# pinghengche.net
KiCad netlist of a schematic drawn in Altium Designer
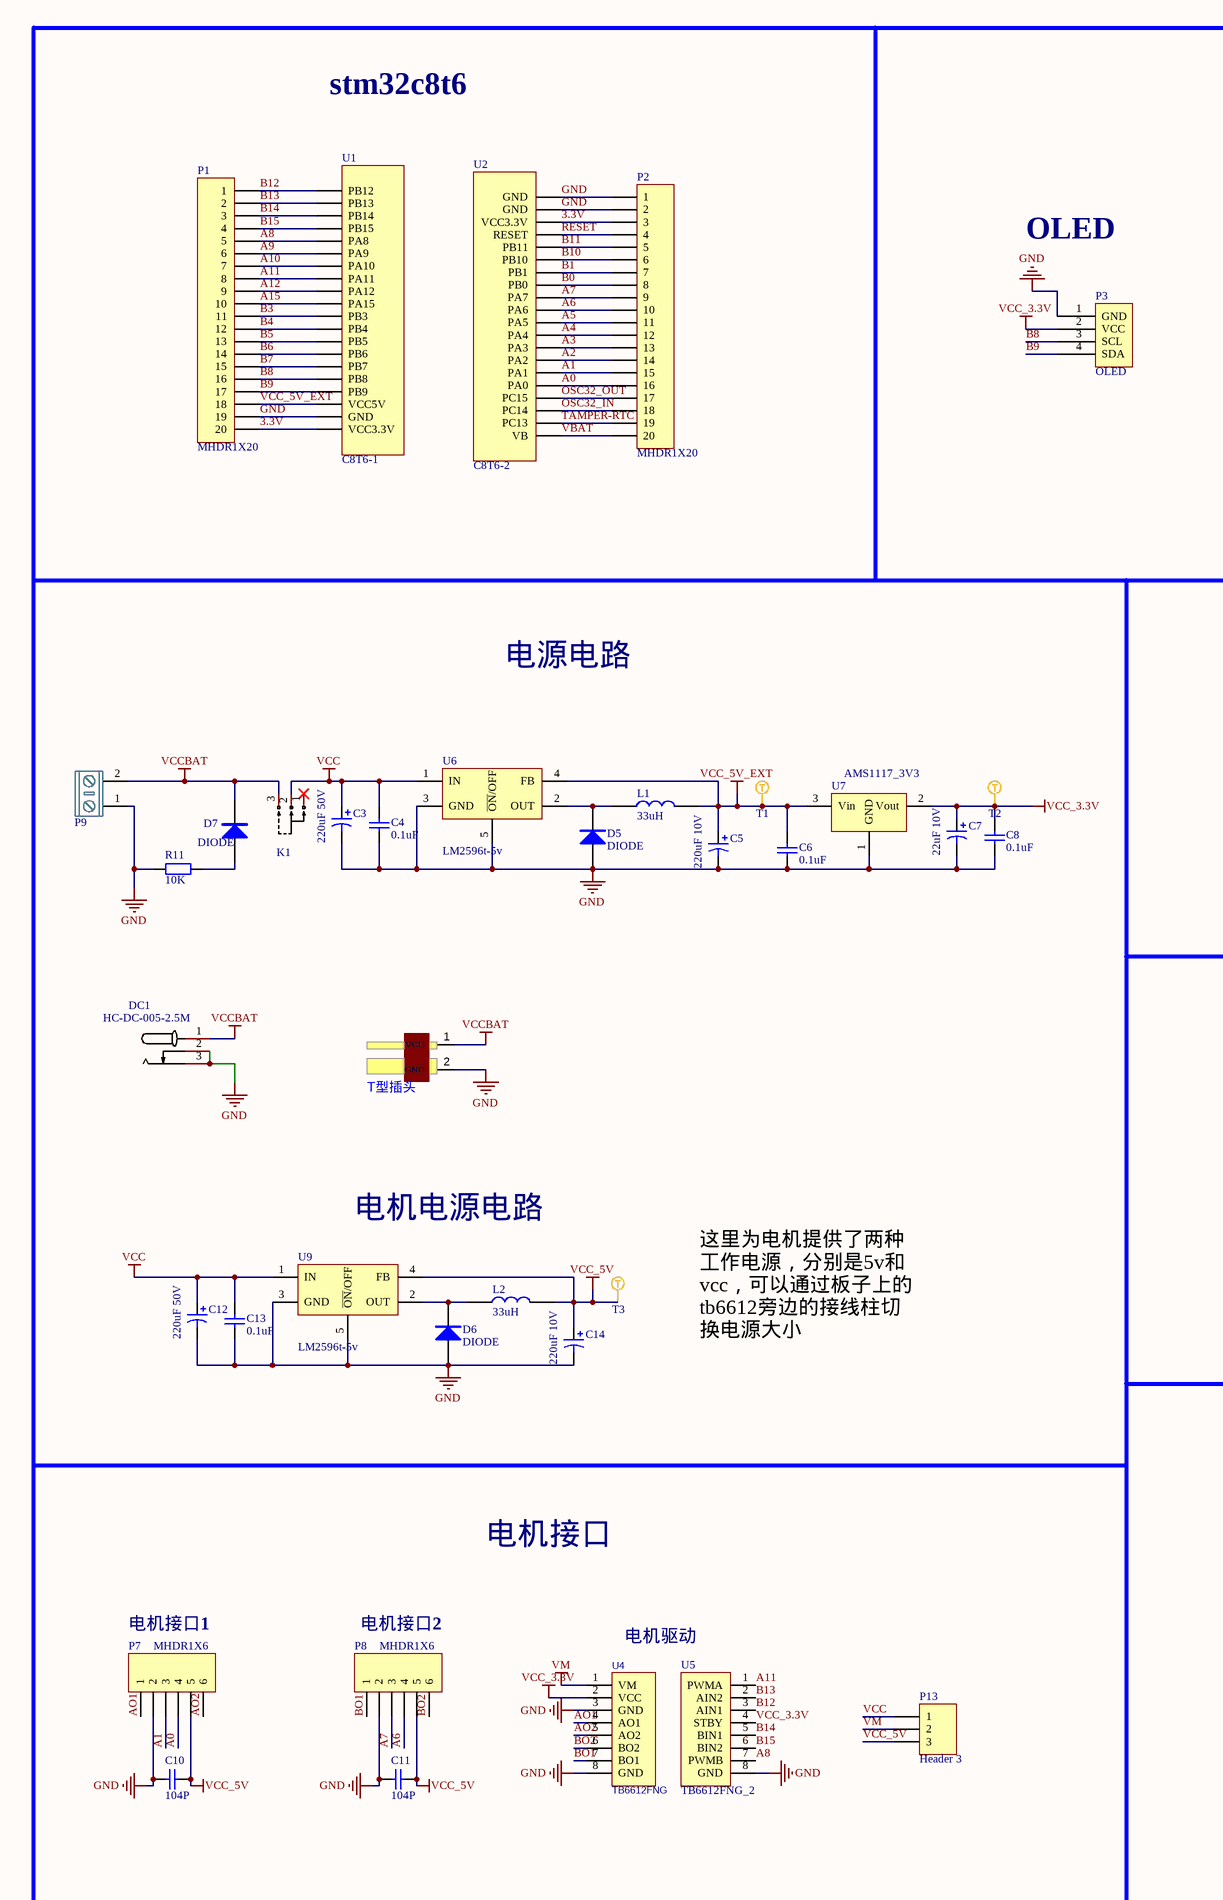
[diagram p0: pinghengche.SchDoc, left]
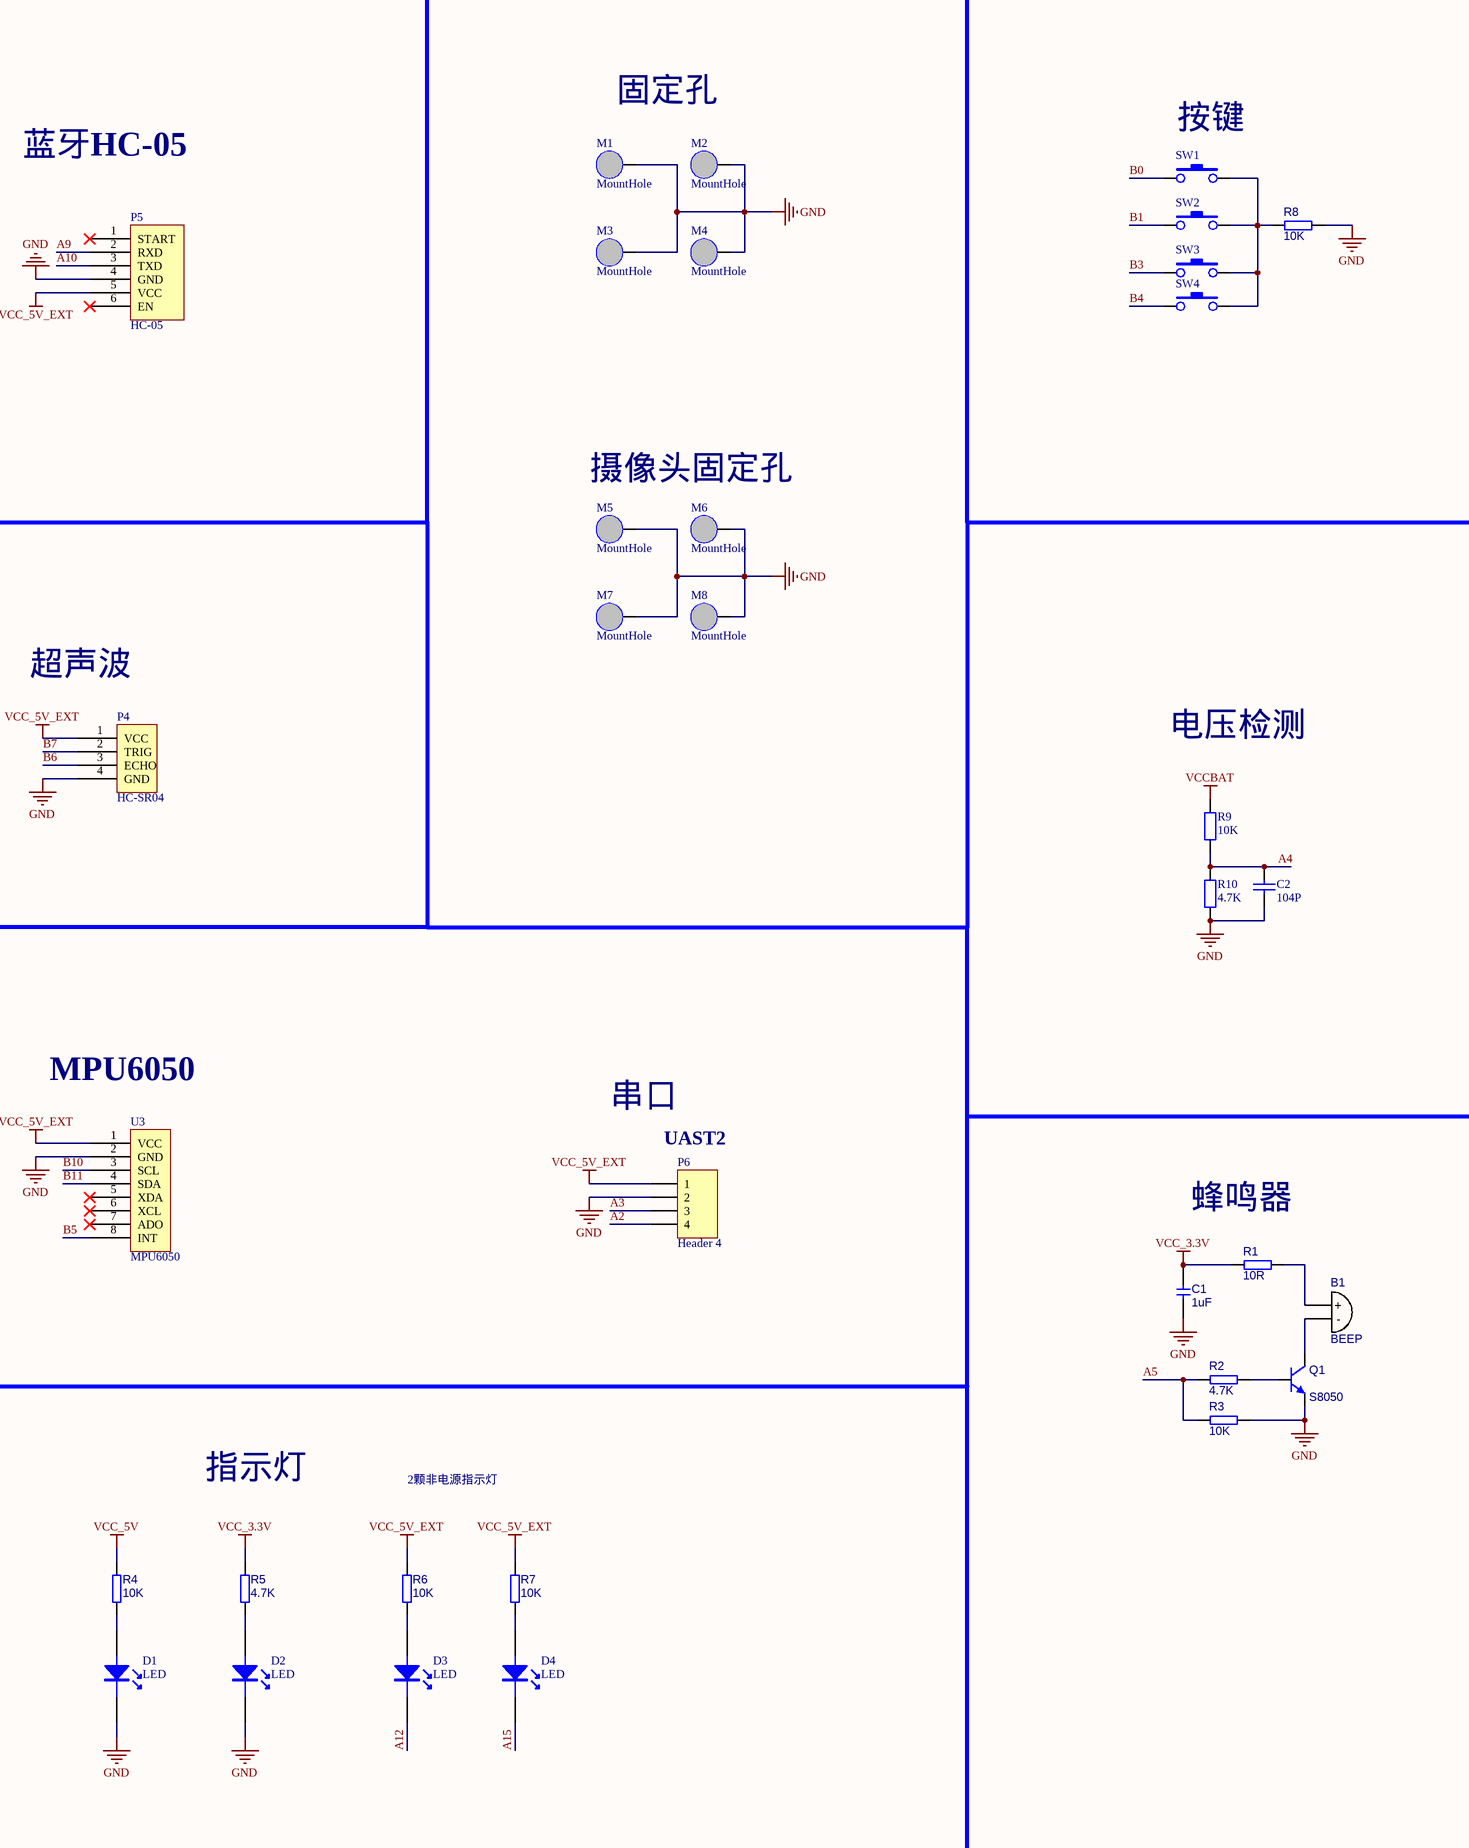
[diagram p1: pinghengche.SchDoc, right]

(export (version "E")
  (design (tool "Eeschema 10.0.6"))
  (components
    (comp (ref "B1")
      (value "BEEP")
      (footprint "BEEP 9x5.5mm")
      (description "蜂鸣器")
      (libsource (lib "pinghengchezihua") (part "BEEP"))
    )
    (comp (ref "C1")
      (value "1uF")
      (footprint "C0805")
      (description "贴片电容0805")
      (fields (field (name "Comment") "1uF  "))
      (libsource (lib "pinghengchezihua") (part "1uF 080516V X7R"))
    )
    (comp (ref "C2")
      (value "104P")
      (footprint "CAPC1608[0603]S-L")
      (description "0.1uf 贴片电容/MLCC电容")
      (libsource (lib "平衡小车") (part "C"))
    )
    (comp (ref "C3")
      (value "220uF 50V")
      (footprint "CAP-SMD_BD10.0-L10.3-W10.3-LS11.3-FD")
      (description "Polarized Capacitor (Radial)")
      (fields (field (name "Comment") "Cap Pol1") (field (name "PUBLISHER") "Altium Limited"))
      (libsource (lib "Miscellaneous Devices") (part "Cap Pol1"))
    )
    (comp (ref "C4")
      (value "0.1uF")
      (footprint "CAPC1608[0603]S-L")
      (description "Capacitor")
      (fields (field (name "Comment") "Cap") (field (name "PUBLISHER") "Altium Limited"))
      (libsource (lib "Miscellaneous Devices") (part "Cap"))
    )
    (comp (ref "C5")
      (value "220uF 10V")
      (footprint "7343")
      (description "Polarized Capacitor (Radial)")
      (fields (field (name "Comment") "Cap Pol1") (field (name "PUBLISHER") "Altium Limited"))
      (libsource (lib "Miscellaneous Devices") (part "Cap Pol1"))
    )
    (comp (ref "C6")
      (value "0.1uF")
      (footprint "CAPC1608[0603]S-L")
      (description "Capacitor")
      (fields (field (name "Comment") "Cap") (field (name "PUBLISHER") "Altium Limited"))
      (libsource (lib "Miscellaneous Devices") (part "Cap"))
    )
    (comp (ref "C7")
      (value "22uF 10V")
      (footprint "C3528")
      (description "Polarized Capacitor (Radial)")
      (fields (field (name "Comment") "Cap Pol1") (field (name "PUBLISHER") "Altium Limited"))
      (libsource (lib "Miscellaneous Devices") (part "Cap Pol1"))
    )
    (comp (ref "C8")
      (value "0.1uF")
      (footprint "CAPC1608[0603]S-L")
      (description "Capacitor")
      (fields (field (name "Comment") "Cap") (field (name "PUBLISHER") "Altium Limited"))
      (libsource (lib "Miscellaneous Devices") (part "Cap"))
    )
    (comp (ref "C10")
      (value "104P")
      (footprint "CAPC1608[0603]S-L")
      (description "0.1uf 贴片电容/MLCC电容")
      (libsource (lib "平衡小车") (part "C"))
    )
    (comp (ref "C11")
      (value "104P")
      (footprint "CAPC1608[0603]S-L")
      (description "0.1uf 贴片电容/MLCC电容")
      (libsource (lib "平衡小车") (part "C"))
    )
    (comp (ref "C12")
      (value "220uF 50V")
      (footprint "CAP-SMD_BD10.0-L10.3-W10.3-LS11.3-FD")
      (description "Polarized Capacitor (Radial)")
      (fields (field (name "Comment") "Cap Pol1") (field (name "PUBLISHER") "Altium Limited"))
      (libsource (lib "Miscellaneous Devices") (part "Cap Pol1"))
    )
    (comp (ref "C13")
      (value "0.1uF")
      (footprint "CAPC1608[0603]S-L")
      (description "Capacitor")
      (fields (field (name "Comment") "Cap") (field (name "PUBLISHER") "Altium Limited"))
      (libsource (lib "Miscellaneous Devices") (part "Cap"))
    )
    (comp (ref "C14")
      (value "220uF 10V")
      (footprint "7343")
      (description "Polarized Capacitor (Radial)")
      (fields (field (name "Comment") "Cap Pol1") (field (name "PUBLISHER") "Altium Limited"))
      (libsource (lib "Miscellaneous Devices") (part "Cap Pol1"))
    )
    (comp (ref "D1")
      (value "LED")
      (footprint "LED 0805G")
      (description "0805")
      (libsource (lib "pinghengchezihua") (part "LED"))
    )
    (comp (ref "D2")
      (value "LED")
      (footprint "LED 0805G")
      (description "0805")
      (libsource (lib "pinghengchezihua") (part "LED"))
    )
    (comp (ref "D3")
      (value "LED")
      (footprint "LED 0805G")
      (description "0805")
      (libsource (lib "pinghengchezihua") (part "LED"))
    )
    (comp (ref "D4")
      (value "LED")
      (footprint "LED 0805G")
      (description "0805")
      (libsource (lib "pinghengchezihua") (part "LED"))
    )
    (comp (ref "D5") (value "DIODE") (footprint "SS34") (libsource (lib "平衡小车") (part "DIODE")))
    (comp (ref "D6") (value "DIODE") (footprint "SS34") (libsource (lib "平衡小车") (part "DIODE")))
    (comp (ref "D7") (value "DIODE") (footprint "SS34") (libsource (lib "平衡小车") (part "DIODE")))
    (comp (ref "DC1")
      (value "HC-DC-005-2.5M")
      (footprint "DC-005")
      (fields (field (name "NAME") "HC-DC-005-2.5M") (field (name "MANUFACTURER") "HCTL(华灿天禄)"))
      (libsource (lib "altium-import") (part "root_0_HC-DC-005-2.5M_"))
    )
    (comp (ref "DCIN1")
      (value "T型插头")
      (footprint "Wired T-Header ThroughHole")
      (libsource (lib "pinghengchezihua") (part "T_Header"))
    )
    (comp (ref "K1")
      (value "HX SS12D10G4")
      (footprint "SS12D10")
      (description "单刀三档开关")
      (fields (field (name "MANUFACTURER") "hanxia(韩下)"))
      (libsource (lib "changyongwenyadianyuanmokuaixiugai") (part "HX SS12D10G4"))
    )
    (comp (ref "L1") (value "33uH") (footprint "0630 TPC 7*7*3") (libsource (lib "平衡小车") (part "Inductor")))
    (comp (ref "L2") (value "33uH") (footprint "0630 TPC 7*7*3") (libsource (lib "平衡小车") (part "Inductor")))
    (comp (ref "M1")
      (value "MountHole")
      (footprint "M3-MountHole")
      (description "固定孔")
      (libsource (lib "pinghengchezihua") (part "MountHole"))
    )
    (comp (ref "M2")
      (value "MountHole")
      (footprint "M3-MountHole")
      (description "固定孔")
      (libsource (lib "pinghengchezihua") (part "MountHole"))
    )
    (comp (ref "M3")
      (value "MountHole")
      (footprint "M3-MountHole")
      (description "固定孔")
      (libsource (lib "pinghengchezihua") (part "MountHole"))
    )
    (comp (ref "M4")
      (value "MountHole")
      (footprint "M3-MountHole")
      (description "固定孔")
      (libsource (lib "pinghengchezihua") (part "MountHole"))
    )
    (comp (ref "M5")
      (value "MountHole")
      (footprint "M3-MountHole")
      (description "固定孔")
      (libsource (lib "pinghengchezihua") (part "MountHole"))
    )
    (comp (ref "M6")
      (value "MountHole")
      (footprint "M3-MountHole")
      (description "固定孔")
      (libsource (lib "pinghengchezihua") (part "MountHole"))
    )
    (comp (ref "M7")
      (value "MountHole")
      (footprint "M3-MountHole")
      (description "固定孔")
      (libsource (lib "pinghengchezihua") (part "MountHole"))
    )
    (comp (ref "M8")
      (value "MountHole")
      (footprint "M3-MountHole")
      (description "固定孔")
      (libsource (lib "pinghengchezihua") (part "MountHole"))
    )
    (comp (ref "P1")
      (value "MHDR1X20")
      (footprint "HDR2.54-LI-20P")
      (description "Header, 20-Pin")
      (fields (field (name "PUBLISHER") "Altium Limited"))
      (libsource (lib "pinghengchezihua") (part "MHDR1X20"))
    )
    (comp (ref "P2")
      (value "MHDR1X20")
      (footprint "HDR2.54-LI-20P")
      (description "Header, 20-Pin")
      (fields (field (name "PUBLISHER") "Altium Limited"))
      (libsource (lib "") (part "MHDR1X20_1"))
    )
    (comp (ref "P3")
      (value "OLED")
      (footprint "OLED4p")
      (description "0.96寸OLED屏，GND开头")
      (libsource (lib "pinghengchezihua_1") (part "0.96OLED"))
    )
    (comp (ref "P4")
      (value "HC-SR04")
      (footprint "HC-SR04")
      (description "超声波HC-SR04")
      (libsource (lib "pinghengchezihua") (part "HC-SR04"))
    )
    (comp (ref "P5")
      (value "HC-05")
      (footprint "HDR-TH_6P-P2.54-V-F")
      (description "HC-05 这里只用到了其4个管脚")
      (libsource (lib "pinghengchezihua") (part "HC-05"))
    )
    (comp (ref "P6")
      (value "Header 4")
      (footprint "HDR1X4-M")
      (description "Header, 4-Pin")
      (fields (field (name "PUBLISHER") "Altium Limited"))
      (libsource (lib "pinghengchezihua") (part "Header 4"))
    )
    (comp (ref "P7")
      (value "MHDR1X6")
      (footprint "XH2.54-WI-6P")
      (description "Header, 6-Pin")
      (fields (field (name "PUBLISHER") "Altium Limited"))
      (libsource (lib "pinghengchezihua") (part "MHDR1X6"))
    )
    (comp (ref "P8")
      (value "MHDR1X6")
      (footprint "XH2.54-WI-6P")
      (description "Header, 6-Pin")
      (fields (field (name "PUBLISHER") "Altium Limited"))
      (libsource (lib "pinghengchezihua") (part "MHDR1X6"))
    )
    (comp (ref "P9")
      (value "KF/WJ/DG 30x connecter")
      (footprint "KF/WJ/DG 301-2p-5.0mm")
      (description "接线端子 2Pin")
      (libsource (lib "RT1064 主板 V3.0 器件封装集成库") (part "KF/WJ/DG 30x"))
    )
    (comp (ref "P13")
      (value "Header 3")
      (footprint "HDR-TH_3P-P2.54-V-M-1")
      (description "Header, 3-Pin")
      (fields (field (name "PUBLISHER") "Altium Limited"))
      (libsource (lib "pinghengchezihua") (part "Header 3"))
    )
    (comp (ref "Q1")
      (value "S8050")
      (footprint "SOT-23")
      (description "Discrete NPN Bipolar Transistor")
      (fields (field (name "PARTNUMBER") "S8050") (field (name "PUBLISHER") "Altium Limited"))
      (libsource (lib "pinghengchezihua") (part "NPN S8050"))
    )
    (comp (ref "R1")
      (value "10R")
      (footprint "R0603")
      (description "贴片电阻")
      (fields (field (name "TOLERANCE") "±1%") (field (name "Comment") "10R ±1%"))
      (libsource (lib "pinghengchezihua") (part "Res-Chip_10"))
    )
    (comp (ref "R2")
      (value "4.7K")
      (footprint "RESC1608[0603]S-L")
      (description "贴片电阻")
      (fields (field (name "POWER") "1/8W") (field (name "TOLERANCE") "±1%"))
      (libsource (lib "pinghengchezihua") (part "Res-Chip_9"))
    )
    (comp (ref "R3")
      (value "10K")
      (footprint "RESC1608[0603]S-L")
      (description "贴片电阻")
      (fields (field (name "POWER") "1/8W") (field (name "TOLERANCE") "±1%"))
      (libsource (lib "pinghengchezihua") (part "Res-Chip"))
    )
    (comp (ref "R4")
      (value "10K")
      (footprint "RESC1608[0603]S-L")
      (description "贴片电阻")
      (fields (field (name "POWER") "1/8W") (field (name "TOLERANCE") "±1%"))
      (libsource (lib "pinghengchezihua") (part "Res-Chip"))
    )
    (comp (ref "R5")
      (value "4.7K")
      (footprint "RESC1608[0603]S-L")
      (description "贴片电阻")
      (fields (field (name "POWER") "1/8W") (field (name "TOLERANCE") "±1%"))
      (libsource (lib "pinghengchezihua") (part "Res-Chip_9"))
    )
    (comp (ref "R6")
      (value "10K")
      (footprint "RESC1608[0603]S-L")
      (description "贴片电阻")
      (fields (field (name "POWER") "1/8W") (field (name "TOLERANCE") "±1%"))
      (libsource (lib "pinghengchezihua") (part "Res-Chip"))
    )
    (comp (ref "R7")
      (value "10K")
      (footprint "RESC1608[0603]S-L")
      (description "贴片电阻")
      (fields (field (name "POWER") "1/8W") (field (name "TOLERANCE") "±1%"))
      (libsource (lib "pinghengchezihua") (part "Res-Chip"))
    )
    (comp (ref "R8")
      (value "10K")
      (footprint "RESC1608[0603]S-L")
      (description "贴片电阻")
      (fields (field (name "POWER") "1/8W") (field (name "TOLERANCE") "±1%"))
      (libsource (lib "pinghengchezihua") (part "Res-Chip"))
    )
    (comp (ref "R9")
      (value "10K")
      (footprint "RESC1608[0603]S-L")
      (description "贴片电阻")
      (libsource (lib "平衡小车") (part "R"))
    )
    (comp (ref "R10")
      (value "4.7K")
      (footprint "RESC1608[0603]S-L")
      (description "贴片电阻")
      (libsource (lib "平衡小车") (part "R"))
    )
    (comp (ref "R11")
      (value "10K")
      (footprint "RESC1608[0603]S-L")
      (description "贴片电阻")
      (libsource (lib "平衡小车") (part "R"))
    )
    (comp (ref "SW1")
      (value "SW-PB_V")
      (footprint "TSW SMD-3*6*2.5")
      (description "SWITCH")
      (libsource (lib "pinghengchezihua") (part "SW-PB_V"))
    )
    (comp (ref "SW2")
      (value "SW-PB_V")
      (footprint "TSW SMD-3*6*2.5")
      (description "SWITCH")
      (libsource (lib "pinghengchezihua") (part "SW-PB_V"))
    )
    (comp (ref "SW3")
      (value "SW-PB_V")
      (footprint "TSW SMD-3*6*2.5")
      (description "SWITCH")
      (libsource (lib "pinghengchezihua") (part "SW-PB_V"))
    )
    (comp (ref "SW4")
      (value "SW-PB_V")
      (footprint "TSW SMD-3*6*2.5")
      (description "SWITCH")
      (libsource (lib "pinghengchezihua") (part "SW-PB_V"))
    )
    (comp (ref "T1")
      (value "Testpoint-Pad")
      (footprint "testpoint-pad-1mm")
      (description "测试点，就是个焊盘")
      (libsource (lib "pinghengchezihua") (part "Testpoint-Pad-S"))
    )
    (comp (ref "T2")
      (value "Testpoint-Pad")
      (footprint "testpoint-pad-1mm")
      (description "测试点，就是个焊盘")
      (libsource (lib "pinghengchezihua") (part "Testpoint-Pad-S"))
    )
    (comp (ref "T3")
      (value "Testpoint-Pad")
      (footprint "testpoint-pad-1mm")
      (description "测试点，就是个焊盘")
      (libsource (lib "pinghengchezihua") (part "Testpoint-Pad-S"))
    )
    (comp (ref "U1")
      (value "C8T6-1")
      (footprint "HDR2.54-M-LI-20P")
      (description "stm32f103c8t6扩展接口")
      (libsource (lib "pinghengchezihua") (part "C8T6-1"))
    )
    (comp (ref "U2")
      (value "C8T6-2")
      (footprint "HDR2.54-M-LI-20P")
      (description "stm32f103c8t6扩展接口")
      (libsource (lib "pinghengchezihua") (part "C8T6-2"))
    )
    (comp (ref "U3")
      (value "MPU6050")
      (footprint "HDR2.54-M-LI-8P")
      (description "MPU6050陀螺仪")
      (libsource (lib "pinghengchezihua") (part "MPU6050"))
    )
    (comp (ref "U4")
      (value "TB6612FNG")
      (footprint "HDR2.54-M-LI-8P")
      (description "电机驱动")
      (libsource (lib "pinghengchezihua") (part "TB6612FNG_1"))
    )
    (comp (ref "U5")
      (value "TB6612FNG_2")
      (footprint "HDR2.54-M-LI-8P")
      (libsource (lib "pinghengchezihua_1") (part "TB6612FNG_2"))
    )
    (comp (ref "U6")
      (value "LM2596t-5v")
      (footprint "LM2596-5V")
      (description "Simple Switcher 3A Step Down Voltage Regulator")
      (fields (field (name "PUBLISHER") "Altium Limited"))
      (libsource (lib "pinghengchezihua") (part "LM2596"))
    )
    (comp (ref "U7")
      (value "AMS1117_3V3")
      (footprint "SOT-223")
      (description "3.3V电压转换器AMS1117")
      (libsource (lib "平衡小车") (part "AMS1117_1"))
    )
    (comp (ref "U9")
      (value "LM2596t-5v")
      (footprint "LM2596-5V")
      (description "Simple Switcher 3A Step Down Voltage Regulator")
      (fields (field (name "PUBLISHER") "Altium Limited"))
      (libsource (lib "pinghengchezihua") (part "LM2596"))
    )
  )
  (nets
    (net (code "1") (name "/3.3V") (class "Default")
      (node (ref "P1") (pin "20") (pinfunction "20_20") (pintype "passive"))
      (node (ref "P2") (pin "3") (pinfunction "3_3") (pintype "passive"))
      (node (ref "U1") (pin "20") (pinfunction "VCC3.3V_20") (pintype "passive"))
      (node (ref "U2") (pin "3") (pinfunction "VCC3.3V_3") (pintype "passive"))
    )
    (net (code "2") (name "/A0") (class "Default")
      (node (ref "P2") (pin "16") (pinfunction "16_16") (pintype "passive"))
      (node (ref "P7") (pin "4") (pinfunction "4_4") (pintype "passive"))
      (node (ref "U2") (pin "16") (pinfunction "PA0_16") (pintype "passive"))
    )
    (net (code "3") (name "/A1") (class "Default")
      (node (ref "P2") (pin "15") (pinfunction "15_15") (pintype "passive"))
      (node (ref "P7") (pin "3") (pinfunction "3_3") (pintype "passive"))
      (node (ref "U2") (pin "15") (pinfunction "PA1_15") (pintype "passive"))
    )
    (net (code "4") (name "/A2") (class "Default")
      (node (ref "P2") (pin "14") (pinfunction "14_14") (pintype "passive"))
      (node (ref "P6") (pin "4") (pinfunction "4_4") (pintype "passive"))
      (node (ref "U2") (pin "14") (pinfunction "PA2_14") (pintype "passive"))
    )
    (net (code "5") (name "/A3") (class "Default")
      (node (ref "P2") (pin "13") (pinfunction "13_13") (pintype "passive"))
      (node (ref "P6") (pin "3") (pinfunction "3_3") (pintype "passive"))
      (node (ref "U2") (pin "13") (pinfunction "PA3_13") (pintype "passive"))
    )
    (net (code "6") (name "/A4") (class "Default")
      (node (ref "C2") (pin "1") (pinfunction "1_1") (pintype "passive"))
      (node (ref "P2") (pin "12") (pinfunction "12_12") (pintype "passive"))
      (node (ref "R10") (pin "2") (pinfunction "2_2") (pintype "passive"))
      (node (ref "R9") (pin "1") (pinfunction "1_1") (pintype "passive"))
      (node (ref "U2") (pin "12") (pinfunction "PA4_12") (pintype "passive"))
    )
    (net (code "7") (name "/A5") (class "Default")
      (node (ref "P2") (pin "11") (pinfunction "11_11") (pintype "passive"))
      (node (ref "R2") (pin "1") (pinfunction "1_1") (pintype "passive"))
      (node (ref "R3") (pin "1") (pinfunction "1_1") (pintype "passive"))
      (node (ref "U2") (pin "11") (pinfunction "PA5_11") (pintype "passive"))
    )
    (net (code "8") (name "/A6") (class "Default")
      (node (ref "P2") (pin "10") (pinfunction "10_10") (pintype "passive"))
      (node (ref "P8") (pin "4") (pinfunction "4_4") (pintype "passive"))
      (node (ref "U2") (pin "10") (pinfunction "PA6_10") (pintype "passive"))
    )
    (net (code "9") (name "/A7") (class "Default")
      (node (ref "P2") (pin "9") (pinfunction "9_9") (pintype "passive"))
      (node (ref "P8") (pin "3") (pinfunction "3_3") (pintype "passive"))
      (node (ref "U2") (pin "9") (pinfunction "PA7_9") (pintype "passive"))
    )
    (net (code "10") (name "/A8") (class "Default")
      (node (ref "P1") (pin "5") (pinfunction "5_5") (pintype "passive"))
      (node (ref "U1") (pin "5") (pinfunction "PA8_5") (pintype "passive"))
      (node (ref "U5") (pin "7") (pinfunction "PWMB_7") (pintype "passive"))
    )
    (net (code "11") (name "/A9") (class "Default")
      (node (ref "P1") (pin "6") (pinfunction "6_6") (pintype "passive"))
      (node (ref "P5") (pin "2") (pinfunction "RXD_2") (pintype "passive"))
      (node (ref "U1") (pin "6") (pinfunction "PA9_6") (pintype "passive"))
    )
    (net (code "12") (name "/A10") (class "Default")
      (node (ref "P1") (pin "7") (pinfunction "7_7") (pintype "passive"))
      (node (ref "P5") (pin "3") (pinfunction "TXD_3") (pintype "passive"))
      (node (ref "U1") (pin "7") (pinfunction "PA10_7") (pintype "passive"))
    )
    (net (code "13") (name "/A11") (class "Default")
      (node (ref "P1") (pin "8") (pinfunction "8_8") (pintype "passive"))
      (node (ref "U1") (pin "8") (pinfunction "PA11_8") (pintype "passive"))
      (node (ref "U5") (pin "1") (pinfunction "PWMA_1") (pintype "passive"))
    )
    (net (code "14") (name "/A12") (class "Default")
      (node (ref "D3") (pin "2") (pinfunction "2_2") (pintype "passive"))
      (node (ref "P1") (pin "9") (pinfunction "9_9") (pintype "passive"))
      (node (ref "U1") (pin "9") (pinfunction "PA12_9") (pintype "passive"))
    )
    (net (code "15") (name "/A15") (class "Default")
      (node (ref "D4") (pin "2") (pinfunction "2_2") (pintype "passive"))
      (node (ref "P1") (pin "10") (pinfunction "10_10") (pintype "passive"))
      (node (ref "U1") (pin "10") (pinfunction "PA15_10") (pintype "passive"))
    )
    (net (code "16") (name "/AO1") (class "Default")
      (node (ref "P7") (pin "1") (pinfunction "1_1") (pintype "passive"))
      (node (ref "U4") (pin "4") (pinfunction "AO1_4") (pintype "passive"))
    )
    (net (code "17") (name "/AO2") (class "Default")
      (node (ref "P7") (pin "6") (pinfunction "6_6") (pintype "passive"))
      (node (ref "U4") (pin "5") (pinfunction "AO2_5") (pintype "passive"))
    )
    (net (code "18") (name "/B0") (class "Default")
      (node (ref "P2") (pin "8") (pinfunction "8_8") (pintype "passive"))
      (node (ref "SW1") (pin "1") (pinfunction "1_1") (pintype "passive"))
      (node (ref "U2") (pin "8") (pinfunction "PB0_8") (pintype "passive"))
    )
    (net (code "19") (name "/B1") (class "Default")
      (node (ref "P2") (pin "7") (pinfunction "7_7") (pintype "passive"))
      (node (ref "SW2") (pin "1") (pinfunction "1_1") (pintype "passive"))
      (node (ref "U2") (pin "7") (pinfunction "PB1_7") (pintype "passive"))
    )
    (net (code "20") (name "/B3") (class "Default")
      (node (ref "P1") (pin "11") (pinfunction "11_11") (pintype "passive"))
      (node (ref "SW3") (pin "1") (pinfunction "1_1") (pintype "passive"))
      (node (ref "U1") (pin "11") (pinfunction "PB3_11") (pintype "passive"))
    )
    (net (code "21") (name "/B4") (class "Default")
      (node (ref "P1") (pin "12") (pinfunction "12_12") (pintype "passive"))
      (node (ref "SW4") (pin "1") (pinfunction "1_1") (pintype "passive"))
      (node (ref "U1") (pin "12") (pinfunction "PB4_12") (pintype "passive"))
    )
    (net (code "22") (name "/B5") (class "Default")
      (node (ref "P1") (pin "13") (pinfunction "13_13") (pintype "passive"))
      (node (ref "U1") (pin "13") (pinfunction "PB5_13") (pintype "passive"))
      (node (ref "U3") (pin "8") (pinfunction "INT_8") (pintype "passive"))
    )
    (net (code "23") (name "/B6") (class "Default")
      (node (ref "P1") (pin "14") (pinfunction "14_14") (pintype "passive"))
      (node (ref "P4") (pin "3") (pinfunction "ECHO_3") (pintype "passive"))
      (node (ref "U1") (pin "14") (pinfunction "PB6_14") (pintype "passive"))
    )
    (net (code "24") (name "/B7") (class "Default")
      (node (ref "P1") (pin "15") (pinfunction "15_15") (pintype "passive"))
      (node (ref "P4") (pin "2") (pinfunction "TRIG_2") (pintype "passive"))
      (node (ref "U1") (pin "15") (pinfunction "PB7_15") (pintype "passive"))
    )
    (net (code "25") (name "/B8") (class "Default")
      (node (ref "P1") (pin "16") (pinfunction "16_16") (pintype "passive"))
      (node (ref "P3") (pin "3") (pinfunction "SCL_3") (pintype "passive"))
      (node (ref "U1") (pin "16") (pinfunction "PB8_16") (pintype "passive"))
    )
    (net (code "26") (name "/B9") (class "Default")
      (node (ref "P1") (pin "17") (pinfunction "17_17") (pintype "passive"))
      (node (ref "P3") (pin "4") (pinfunction "SDA_4") (pintype "passive"))
      (node (ref "U1") (pin "17") (pinfunction "PB9_17") (pintype "passive"))
    )
    (net (code "27") (name "/B10") (class "Default")
      (node (ref "P2") (pin "6") (pinfunction "6_6") (pintype "passive"))
      (node (ref "U2") (pin "6") (pinfunction "PB10_6") (pintype "passive"))
      (node (ref "U3") (pin "3") (pinfunction "SCL_3") (pintype "passive"))
    )
    (net (code "28") (name "/B11") (class "Default")
      (node (ref "P2") (pin "5") (pinfunction "5_5") (pintype "passive"))
      (node (ref "U2") (pin "5") (pinfunction "PB11_5") (pintype "passive"))
      (node (ref "U3") (pin "4") (pinfunction "SDA_4") (pintype "passive"))
    )
    (net (code "29") (name "/B12") (class "Default")
      (node (ref "P1") (pin "1") (pinfunction "1_1") (pintype "passive"))
      (node (ref "U1") (pin "1") (pinfunction "PB12_1") (pintype "passive"))
      (node (ref "U5") (pin "3") (pinfunction "AIN1_3") (pintype "passive"))
    )
    (net (code "30") (name "/B13") (class "Default")
      (node (ref "P1") (pin "2") (pinfunction "2_2") (pintype "passive"))
      (node (ref "U1") (pin "2") (pinfunction "PB13_2") (pintype "passive"))
      (node (ref "U5") (pin "2") (pinfunction "AIN2_2") (pintype "passive"))
    )
    (net (code "31") (name "/B14") (class "Default")
      (node (ref "P1") (pin "3") (pinfunction "3_3") (pintype "passive"))
      (node (ref "U1") (pin "3") (pinfunction "PB14_3") (pintype "passive"))
      (node (ref "U5") (pin "5") (pinfunction "BIN1_5") (pintype "passive"))
    )
    (net (code "32") (name "/B15") (class "Default")
      (node (ref "P1") (pin "4") (pinfunction "4_4") (pintype "passive"))
      (node (ref "U1") (pin "4") (pinfunction "PB15_4") (pintype "passive"))
      (node (ref "U5") (pin "6") (pinfunction "BIN2_6") (pintype "passive"))
    )
    (net (code "33") (name "/BO1") (class "Default")
      (node (ref "P8") (pin "1") (pinfunction "1_1") (pintype "passive"))
      (node (ref "U4") (pin "7") (pinfunction "BO1_7") (pintype "passive"))
    )
    (net (code "34") (name "/BO2") (class "Default")
      (node (ref "P8") (pin "6") (pinfunction "6_6") (pintype "passive"))
      (node (ref "U4") (pin "6") (pinfunction "BO2_6") (pintype "passive"))
    )
    (net (code "35") (name "/OSC32_IN") (class "Default")
      (node (ref "P2") (pin "18") (pinfunction "18_18") (pintype "passive"))
      (node (ref "U2") (pin "18") (pinfunction "PC14_18") (pintype "passive"))
    )
    (net (code "36") (name "/OSC32_OUT") (class "Default")
      (node (ref "P2") (pin "17") (pinfunction "17_17") (pintype "passive"))
      (node (ref "U2") (pin "17") (pinfunction "PC15_17") (pintype "passive"))
    )
    (net (code "37") (name "/RESET") (class "Default")
      (node (ref "P2") (pin "4") (pinfunction "4_4") (pintype "passive"))
      (node (ref "U2") (pin "4") (pinfunction "RESET_4") (pintype "passive"))
    )
    (net (code "38") (name "/TAMPER-RTC") (class "Default")
      (node (ref "P2") (pin "19") (pinfunction "19_19") (pintype "passive"))
      (node (ref "U2") (pin "19") (pinfunction "PC13_19") (pintype "passive"))
    )
    (net (code "39") (name "/VBAT") (class "Default")
      (node (ref "P2") (pin "20") (pinfunction "20_20") (pintype "passive"))
      (node (ref "U2") (pin "20") (pinfunction "VB_20") (pintype "passive"))
    )
    (net (code "40") (name "GND") (class "Default")
      (node (ref "C1") (pin "1") (pinfunction "1_1") (pintype "passive"))
      (node (ref "C10") (pin "1") (pinfunction "1_1") (pintype "passive"))
      (node (ref "C11") (pin "1") (pinfunction "1_1") (pintype "passive"))
      (node (ref "C12") (pin "2") (pinfunction "2_2") (pintype "passive"))
      (node (ref "C13") (pin "2") (pinfunction "2_2") (pintype "passive"))
      (node (ref "C14") (pin "2") (pinfunction "2_2") (pintype "passive"))
      (node (ref "C2") (pin "2") (pinfunction "2_2") (pintype "passive"))
      (node (ref "C3") (pin "2") (pinfunction "2_2") (pintype "passive"))
      (node (ref "C4") (pin "2") (pinfunction "2_2") (pintype "passive"))
      (node (ref "C5") (pin "2") (pinfunction "2_2") (pintype "passive"))
      (node (ref "C6") (pin "2") (pinfunction "2_2") (pintype "passive"))
      (node (ref "C7") (pin "2") (pinfunction "2_2") (pintype "passive"))
      (node (ref "C8") (pin "2") (pinfunction "2_2") (pintype "passive"))
      (node (ref "D1") (pin "2") (pinfunction "2_2") (pintype "passive"))
      (node (ref "D2") (pin "2") (pinfunction "2_2") (pintype "passive"))
      (node (ref "D5") (pin "1") (pinfunction "1_1") (pintype "passive"))
      (node (ref "D6") (pin "1") (pinfunction "1_1") (pintype "passive"))
      (node (ref "DC1") (pin "2") (pinfunction "2_2") (pintype "passive"))
      (node (ref "DC1") (pin "3") (pinfunction "3_3") (pintype "passive"))
      (node (ref "DCIN1") (pin "2") (pinfunction "GND_2") (pintype "passive"))
      (node (ref "M1") (pin "1") (pinfunction "1_1") (pintype "passive"))
      (node (ref "M2") (pin "1") (pinfunction "1_1") (pintype "passive"))
      (node (ref "M3") (pin "1") (pinfunction "1_1") (pintype "passive"))
      (node (ref "M4") (pin "1") (pinfunction "1_1") (pintype "passive"))
      (node (ref "M5") (pin "1") (pinfunction "1_1") (pintype "passive"))
      (node (ref "M6") (pin "1") (pinfunction "1_1") (pintype "passive"))
      (node (ref "M7") (pin "1") (pinfunction "1_1") (pintype "passive"))
      (node (ref "M8") (pin "1") (pinfunction "1_1") (pintype "passive"))
      (node (ref "P1") (pin "19") (pinfunction "19_19") (pintype "passive"))
      (node (ref "P2") (pin "1") (pinfunction "1_1") (pintype "passive"))
      (node (ref "P2") (pin "2") (pinfunction "2_2") (pintype "passive"))
      (node (ref "P3") (pin "1") (pinfunction "GND_1") (pintype "passive"))
      (node (ref "P4") (pin "4") (pinfunction "GND_4") (pintype "passive"))
      (node (ref "P5") (pin "4") (pinfunction "GND_4") (pintype "passive"))
      (node (ref "P6") (pin "2") (pinfunction "2_2") (pintype "passive"))
      (node (ref "P7") (pin "2") (pinfunction "2_2") (pintype "passive"))
      (node (ref "P8") (pin "2") (pinfunction "2_2") (pintype "passive"))
      (node (ref "P9") (pin "1") (pinfunction "1_1") (pintype "passive"))
      (node (ref "Q1") (pin "2") (pinfunction "E_2") (pintype "passive"))
      (node (ref "R10") (pin "1") (pinfunction "1_1") (pintype "passive"))
      (node (ref "R11") (pin "2") (pinfunction "2_2") (pintype "passive"))
      (node (ref "R3") (pin "2") (pinfunction "2_2") (pintype "passive"))
      (node (ref "R8") (pin "1") (pinfunction "1_1") (pintype "passive"))
      (node (ref "U1") (pin "19") (pinfunction "GND_19") (pintype "passive"))
      (node (ref "U2") (pin "1") (pinfunction "GND_1") (pintype "passive"))
      (node (ref "U2") (pin "2") (pinfunction "GND_2") (pintype "passive"))
      (node (ref "U3") (pin "2") (pinfunction "GND_2") (pintype "passive"))
      (node (ref "U4") (pin "3") (pinfunction "GND_3") (pintype "passive"))
      (node (ref "U4") (pin "8") (pinfunction "GND_8") (pintype "passive"))
      (node (ref "U5") (pin "8") (pinfunction "GND_8") (pintype "passive"))
      (node (ref "U6") (pin "3") (pinfunction "GND_3") (pintype "power_in"))
      (node (ref "U6") (pin "5") (pinfunction "~{ON}/OFF_5") (pintype "passive"))
      (node (ref "U7") (pin "1") (pinfunction "GND_1") (pintype "passive"))
      (node (ref "U9") (pin "3") (pinfunction "GND_3") (pintype "power_in"))
      (node (ref "U9") (pin "5") (pinfunction "~{ON}/OFF_5") (pintype "passive"))
    )
    (net (code "41") (name "Net-(B1-+)") (class "Default")
      (node (ref "B1") (pin "1") (pinfunction "+_1") (pintype "passive"))
      (node (ref "R1") (pin "2") (pinfunction "2_2") (pintype "passive"))
    )
    (net (code "42") (name "Net-(B1--)") (class "Default")
      (node (ref "B1") (pin "2") (pinfunction "-_2") (pintype "passive"))
      (node (ref "Q1") (pin "3") (pinfunction "C_3") (pintype "passive"))
    )
    (net (code "43") (name "Net-(D1-Pad1)") (class "Default")
      (node (ref "D1") (pin "1") (pinfunction "1_1") (pintype "passive"))
      (node (ref "R4") (pin "1") (pinfunction "1_1") (pintype "passive"))
    )
    (net (code "44") (name "Net-(D2-Pad1)") (class "Default")
      (node (ref "D2") (pin "1") (pinfunction "1_1") (pintype "passive"))
      (node (ref "R5") (pin "1") (pinfunction "1_1") (pintype "passive"))
    )
    (net (code "45") (name "Net-(D3-Pad1)") (class "Default")
      (node (ref "D3") (pin "1") (pinfunction "1_1") (pintype "passive"))
      (node (ref "R6") (pin "1") (pinfunction "1_1") (pintype "passive"))
    )
    (net (code "46") (name "Net-(D4-Pad1)") (class "Default")
      (node (ref "D4") (pin "1") (pinfunction "1_1") (pintype "passive"))
      (node (ref "R7") (pin "1") (pinfunction "1_1") (pintype "passive"))
    )
    (net (code "47") (name "Net-(D7-Pad1)") (class "Default")
      (node (ref "D7") (pin "1") (pinfunction "1_1") (pintype "passive"))
      (node (ref "R11") (pin "1") (pinfunction "1_1") (pintype "passive"))
    )
    (net (code "48") (name "Net-(Q1-B)") (class "Default")
      (node (ref "Q1") (pin "1") (pinfunction "B_1") (pintype "passive"))
      (node (ref "R2") (pin "2") (pinfunction "2_2") (pintype "passive"))
    )
    (net (code "49") (name "Net-(R8-Pad2)") (class "Default")
      (node (ref "R8") (pin "2") (pinfunction "2_2") (pintype "passive"))
      (node (ref "SW1") (pin "2") (pinfunction "2_2") (pintype "passive"))
      (node (ref "SW2") (pin "2") (pinfunction "2_2") (pintype "passive"))
      (node (ref "SW3") (pin "2") (pinfunction "2_2") (pintype "passive"))
      (node (ref "SW4") (pin "2") (pinfunction "2_2") (pintype "passive"))
    )
    (net (code "50") (name "Net-(U6-OUT)") (class "Default")
      (node (ref "D5") (pin "2") (pinfunction "2_2") (pintype "passive"))
      (node (ref "L1") (pin "1") (pinfunction "1_1") (pintype "passive"))
      (node (ref "U6") (pin "2") (pinfunction "OUT_2") (pintype "power_in"))
    )
    (net (code "51") (name "Net-(U9-OUT)") (class "Default")
      (node (ref "D6") (pin "2") (pinfunction "2_2") (pintype "passive"))
      (node (ref "L2") (pin "1") (pinfunction "1_1") (pintype "passive"))
      (node (ref "U9") (pin "2") (pinfunction "OUT_2") (pintype "power_in"))
    )
    (net (code "52") (name "VCC") (class "Default")
      (node (ref "C12") (pin "1") (pinfunction "1_1") (pintype "passive"))
      (node (ref "C13") (pin "1") (pinfunction "1_1") (pintype "passive"))
      (node (ref "C3") (pin "1") (pinfunction "1_1") (pintype "passive"))
      (node (ref "C4") (pin "1") (pinfunction "1_1") (pintype "passive"))
      (node (ref "K1") (pin "2") (pinfunction "2_2") (pintype "passive"))
      (node (ref "P13") (pin "1") (pinfunction "1_1") (pintype "passive"))
      (node (ref "U6") (pin "1") (pinfunction "IN_1") (pintype "power_in"))
      (node (ref "U9") (pin "1") (pinfunction "IN_1") (pintype "power_in"))
    )
    (net (code "53") (name "VCCBAT") (class "Default")
      (node (ref "D7") (pin "2") (pinfunction "2_2") (pintype "passive"))
      (node (ref "DC1") (pin "1") (pinfunction "1_1") (pintype "passive"))
      (node (ref "DCIN1") (pin "1") (pinfunction "VCC_1") (pintype "passive"))
      (node (ref "K1") (pin "3") (pinfunction "3_3") (pintype "passive"))
      (node (ref "P9") (pin "2") (pinfunction "2_2") (pintype "passive"))
      (node (ref "R9") (pin "2") (pinfunction "2_2") (pintype "passive"))
    )
    (net (code "54") (name "VCC_3.3V") (class "Default")
      (node (ref "C1") (pin "2") (pinfunction "2_2") (pintype "passive"))
      (node (ref "C7") (pin "1") (pinfunction "1_1") (pintype "passive"))
      (node (ref "C8") (pin "1") (pinfunction "1_1") (pintype "passive"))
      (node (ref "P3") (pin "2") (pinfunction "VCC_2") (pintype "passive"))
      (node (ref "R1") (pin "1") (pinfunction "1_1") (pintype "passive"))
      (node (ref "R5") (pin "2") (pinfunction "2_2") (pintype "passive"))
      (node (ref "T2") (pin "1") (pinfunction "T_1") (pintype "passive"))
      (node (ref "U4") (pin "2") (pinfunction "VCC_2") (pintype "passive"))
      (node (ref "U5") (pin "4") (pinfunction "STBY_4") (pintype "passive"))
      (node (ref "U7") (pin "2") (pinfunction "Vout_2") (pintype "passive"))
    )
    (net (code "55") (name "VCC_5V") (class "Default")
      (node (ref "C10") (pin "2") (pinfunction "2_2") (pintype "passive"))
      (node (ref "C11") (pin "2") (pinfunction "2_2") (pintype "passive"))
      (node (ref "C14") (pin "1") (pinfunction "1_1") (pintype "passive"))
      (node (ref "L2") (pin "2") (pinfunction "2_2") (pintype "passive"))
      (node (ref "P13") (pin "3") (pinfunction "3_3") (pintype "passive"))
      (node (ref "P7") (pin "5") (pinfunction "5_5") (pintype "passive"))
      (node (ref "P8") (pin "5") (pinfunction "5_5") (pintype "passive"))
      (node (ref "R4") (pin "2") (pinfunction "2_2") (pintype "passive"))
      (node (ref "T3") (pin "1") (pinfunction "T_1") (pintype "passive"))
      (node (ref "U9") (pin "4") (pinfunction "FB_4") (pintype "passive"))
    )
    (net (code "56") (name "VCC_5V_EXT") (class "Default")
      (node (ref "C5") (pin "1") (pinfunction "1_1") (pintype "passive"))
      (node (ref "C6") (pin "1") (pinfunction "1_1") (pintype "passive"))
      (node (ref "L1") (pin "2") (pinfunction "2_2") (pintype "passive"))
      (node (ref "P1") (pin "18") (pinfunction "18_18") (pintype "passive"))
      (node (ref "P4") (pin "1") (pinfunction "VCC_1") (pintype "passive"))
      (node (ref "P5") (pin "5") (pinfunction "VCC_5") (pintype "passive"))
      (node (ref "P6") (pin "1") (pinfunction "1_1") (pintype "passive"))
      (node (ref "R6") (pin "2") (pinfunction "2_2") (pintype "passive"))
      (node (ref "R7") (pin "2") (pinfunction "2_2") (pintype "passive"))
      (node (ref "T1") (pin "1") (pinfunction "T_1") (pintype "passive"))
      (node (ref "U1") (pin "18") (pinfunction "VCC5V_18") (pintype "passive"))
      (node (ref "U3") (pin "1") (pinfunction "VCC_1") (pintype "passive"))
      (node (ref "U6") (pin "4") (pinfunction "FB_4") (pintype "passive"))
      (node (ref "U7") (pin "3") (pinfunction "Vin_3") (pintype "passive"))
    )
    (net (code "57") (name "VM") (class "Default")
      (node (ref "P13") (pin "2") (pinfunction "2_2") (pintype "passive"))
      (node (ref "U4") (pin "1") (pinfunction "VM_1") (pintype "passive"))
    )
    (net (code "58") (name "unconnected-(K1-Pad1)") (class "Default")
      (node (ref "K1") (pin "1") (pinfunction "1_1") (pintype "passive+no_connect"))
    )
    (net (code "59") (name "unconnected-(P5-EN-Pad6)") (class "Default")
      (node (ref "P5") (pin "6") (pinfunction "EN_6") (pintype "passive+no_connect"))
    )
    (net (code "60") (name "unconnected-(P5-START-Pad1)") (class "Default")
      (node (ref "P5") (pin "1") (pinfunction "START_1") (pintype "passive+no_connect"))
    )
    (net (code "61") (name "unconnected-(U3-ADO-Pad7)") (class "Default")
      (node (ref "U3") (pin "7") (pinfunction "ADO_7") (pintype "passive+no_connect"))
    )
    (net (code "62") (name "unconnected-(U3-XCL-Pad6)") (class "Default")
      (node (ref "U3") (pin "6") (pinfunction "XCL_6") (pintype "passive+no_connect"))
    )
    (net (code "63") (name "unconnected-(U3-XDA-Pad5)") (class "Default")
      (node (ref "U3") (pin "5") (pinfunction "XDA_5") (pintype "passive+no_connect"))
    )
  )
)
